# Sheet4_Communications.net
KiCad netlist of a schematic drawn in Altium Designer
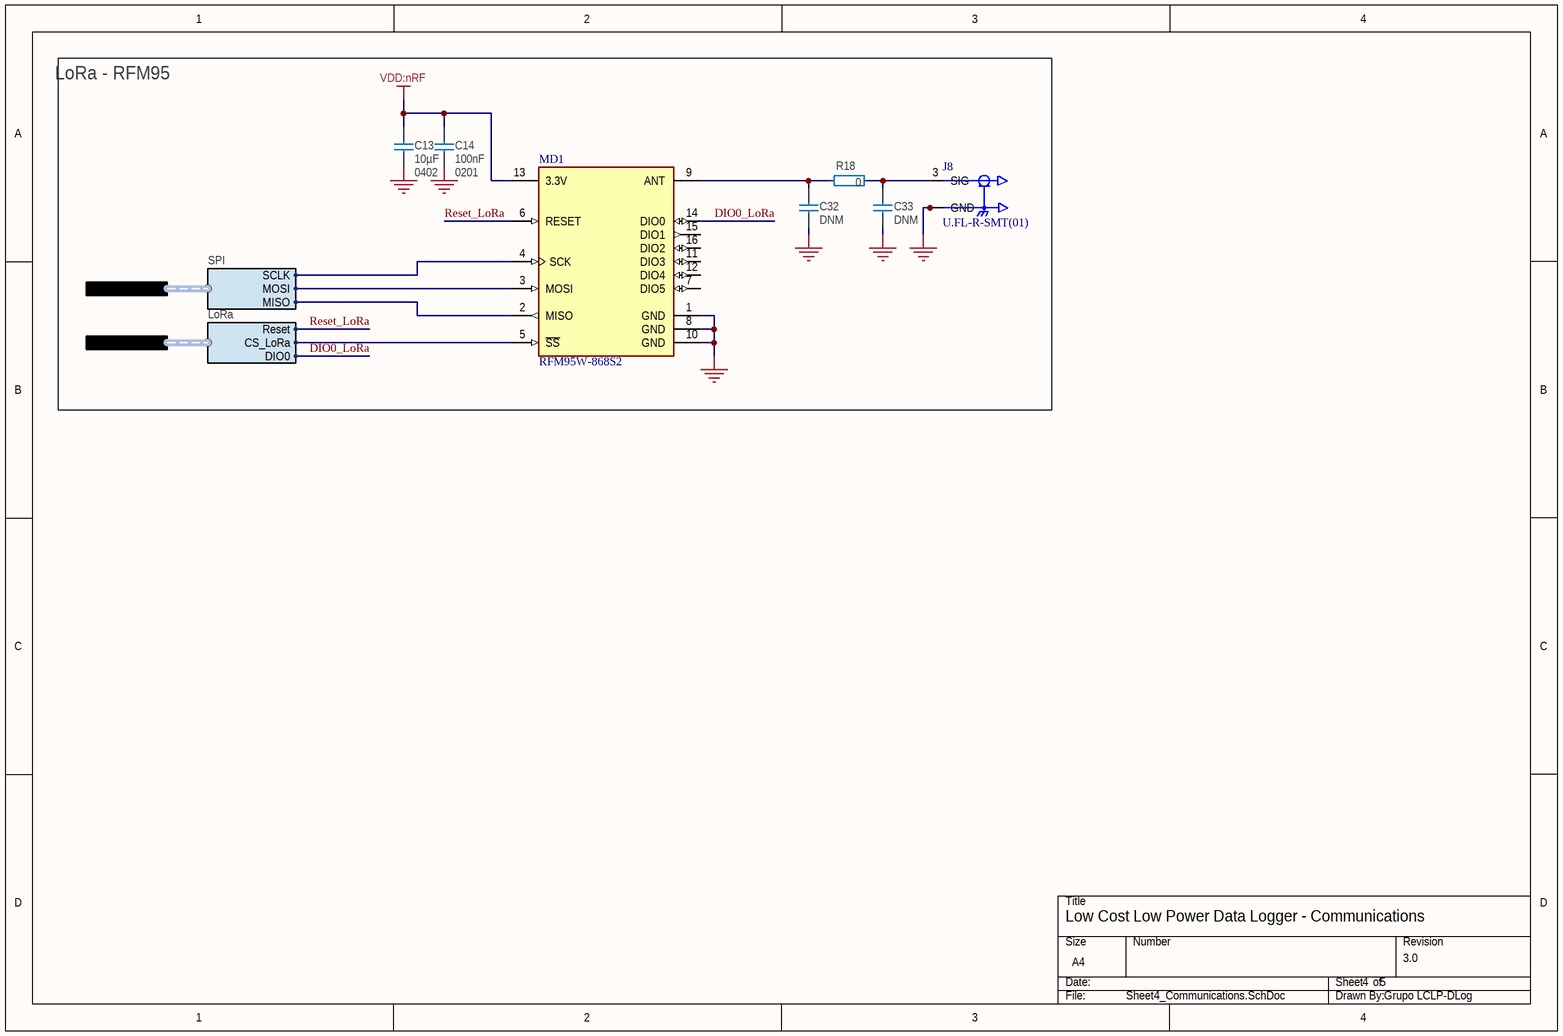
[diagram p0: Sheet4_Communications.SchDoc]

(export (version "E")
  (design (tool "Eeschema 10.0.6"))
  (components
    (comp (ref "C13")
      (value "10µF")
      (footprint "LCLP:CAPC1005X04L")
      (description "Capacitor, X6S, ±20%, 6.3V")
      (fields
        (field (name "PART NUMBER") "C0402-10µF-6.3V-X6S")
        (field (name "MANUFACTURER") "N.A.")
        (field (name "FOOTPRINT DOC") "0402")
        (field (name "AUTHOR") "getr")
      )
      (libsource (lib "AltiumLib") (part "CAP"))
    )
    (comp (ref "C14")
      (value "100nF")
      (footprint "LCLP:CAPC0603X03L_C")
      (description "Capacitor, X7R, ±10%")
      (fields
        (field (name "PART NUMBER") "C0201-100n-10V-X7R")
        (field (name "MANUFACTURER") "N.A.")
        (field (name "FOOTPRINT DOC") "0201")
        (field (name "AUTHOR") "getr")
      )
      (libsource (lib "") (part "CAP_1"))
    )
    (comp (ref "C32")
      (value "DNM")
      (footprint "LCLP:CAPC1005X04L_DNM")
      (description "Capacitor, X5R, ±10%")
      (fields
        (field (name "PART NUMBER") "C0402-2µ2-10V")
        (field (name "MANUFACTURER") "N.A.")
        (field (name "AUTHOR") "rsk")
      )
      (libsource (lib "") (part "CAP_1"))
    )
    (comp (ref "C33")
      (value "DNM")
      (footprint "LCLP:CAPC1005X04L_DNM")
      (description "Capacitor, X5R, ±10%")
      (fields
        (field (name "PART NUMBER") "C0402-2µ2-10V")
        (field (name "MANUFACTURER") "N.A.")
        (field (name "AUTHOR") "rsk")
      )
      (libsource (lib "") (part "CAP_1"))
    )
    (comp (ref "J8")
      (value "U.FL-R-SMT(01)")
      (footprint "HRS_U.FL-R-SMT(01)")
      (fields (field (name "MF") "Hirose"))
      (libsource (lib "Tiago Tavares") (part "U.FL-R-SMT(01)"))
    )
    (comp (ref "MD1")
      (value "RFM95W-868S2")
      (footprint "FP-RFM95W-868S2-MFG")
      (description "RFM95W LoRA Transceiver Module 868MHz")
      (libsource (lib "Tiago Tavares") (part "17626aa6fba47fab2b206b7c140802e"))
    )
    (comp (ref "R18")
      (value "0")
      (footprint "LCLP:RESC1005X04L")
      (description "Resistor, ±1%, 0.05W")
      (fields
        (field (name "PART NUMBER") "R0201-1k0")
        (field (name "MANUFACTURER") "N.A.")
        (field (name "AUTHOR") "rsk")
      )
      (libsource (lib "AltiumLib") (part "RES"))
    )
  )
  (nets
    (net (code "3") (name "/CS_LoRa") (class "Default")
      (node (ref "MD1") (pin "5") (pinfunction "~{SS}_5") (pintype "input"))
    )
    (net (code "4") (name "/DIO0_LoRa") (class "Default")
      (node (ref "MD1") (pin "14") (pinfunction "DIO0_14") (pintype "bidirectional"))
    )
    (net (code "5") (name "/MISO") (class "Default")
      (node (ref "MD1") (pin "2") (pinfunction "MISO_2") (pintype "output"))
    )
    (net (code "6") (name "/MOSI") (class "Default")
      (node (ref "MD1") (pin "3") (pinfunction "MOSI_3") (pintype "input"))
    )
    (net (code "7") (name "/Reset_LoRa") (class "Default")
      (node (ref "MD1") (pin "6") (pinfunction "RESET_6") (pintype "input"))
    )
    (net (code "8") (name "/SCLK") (class "Default")
      (node (ref "MD1") (pin "4") (pinfunction "SCK_4") (pintype "input"))
    )
    (net (code "11") (name "GND") (class "Default")
      (node (ref "C13") (pin "1") (pinfunction "1_1") (pintype "passive"))
      (node (ref "C14") (pin "2") (pinfunction "2_2") (pintype "passive"))
      (node (ref "C32") (pin "1") (pinfunction "1_1") (pintype "passive"))
      (node (ref "C33") (pin "1") (pinfunction "1_1") (pintype "passive"))
      (node (ref "J8") (pin "1") (pinfunction "GND_1") (pintype "passive"))
      (node (ref "J8") (pin "2") (pinfunction "GND_2") (pintype "passive"))
      (node (ref "MD1") (pin "1") (pinfunction "GND_1") (pintype "power_in"))
      (node (ref "MD1") (pin "10") (pinfunction "GND_10") (pintype "power_in"))
      (node (ref "MD1") (pin "8") (pinfunction "GND_8") (pintype "power_in"))
    )
    (net (code "12") (name "Net-(J8-SIG)") (class "Default")
      (node (ref "C33") (pin "2") (pinfunction "2_2") (pintype "passive"))
      (node (ref "J8") (pin "3") (pinfunction "SIG_3") (pintype "passive"))
      (node (ref "R18") (pin "1") (pinfunction "1_1") (pintype "passive"))
    )
    (net (code "13") (name "Net-(MD1-ANT)") (class "Default")
      (node (ref "C32") (pin "2") (pinfunction "2_2") (pintype "passive"))
      (node (ref "MD1") (pin "9") (pinfunction "ANT_9") (pintype "passive"))
      (node (ref "R18") (pin "2") (pinfunction "2_2") (pintype "passive"))
    )
    (net (code "14") (name "VDD:nRF") (class "Default")
      (node (ref "C13") (pin "2") (pinfunction "2_2") (pintype "passive"))
      (node (ref "C14") (pin "1") (pinfunction "1_1") (pintype "passive"))
      (node (ref "MD1") (pin "13") (pinfunction "3.3V_13") (pintype "power_in"))
    )
    (net (code "15") (name "unconnected-(MD1-DIO1-Pad15)") (class "Default")
      (node (ref "MD1") (pin "15") (pinfunction "DIO1_15") (pintype "output"))
    )
    (net (code "16") (name "unconnected-(MD1-DIO2-Pad16)") (class "Default")
      (node (ref "MD1") (pin "16") (pinfunction "DIO2_16") (pintype "bidirectional"))
    )
    (net (code "17") (name "unconnected-(MD1-DIO3-Pad11)") (class "Default")
      (node (ref "MD1") (pin "11") (pinfunction "DIO3_11") (pintype "bidirectional"))
    )
    (net (code "18") (name "unconnected-(MD1-DIO4-Pad12)") (class "Default")
      (node (ref "MD1") (pin "12") (pinfunction "DIO4_12") (pintype "bidirectional"))
    )
    (net (code "19") (name "unconnected-(MD1-DIO5-Pad7)") (class "Default")
      (node (ref "MD1") (pin "7") (pinfunction "DIO5_7") (pintype "bidirectional"))
    )
  )
)
